# more_testing.net
KiCad netlist of a schematic drawn in EAGLE
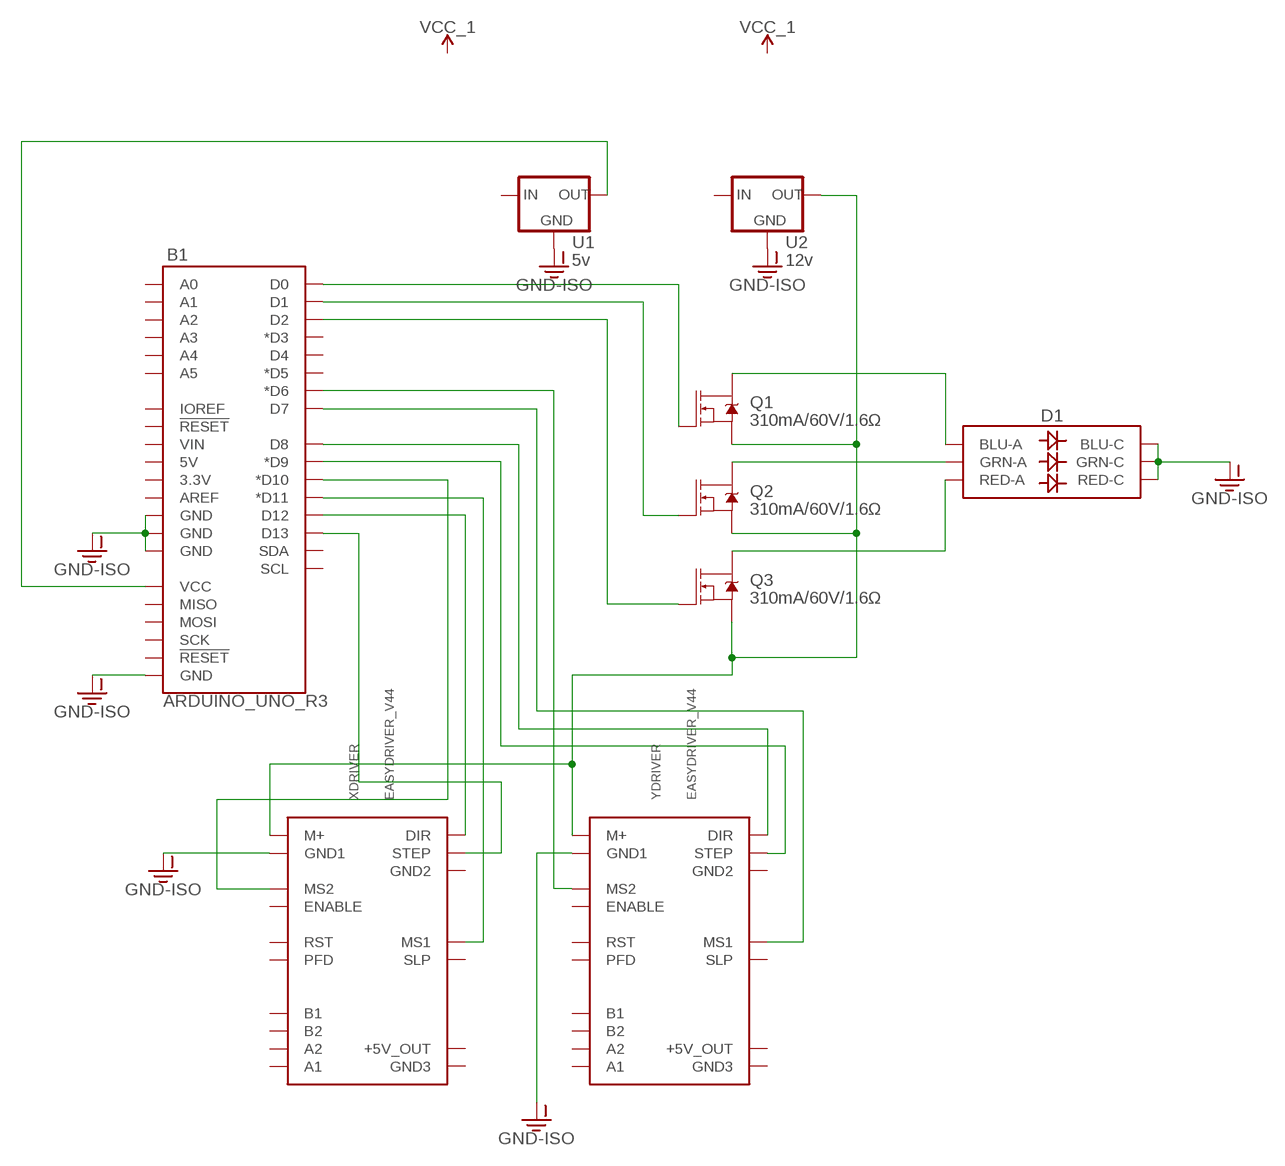
[diagram p0: schematic, sheet 1]

(export (version "E")
  (design (tool "Eeschema 10.0.6"))
  (components
    (comp (ref "B1")
      (value "ARDUINO_UNO_R3")
      (footprint "eagle-import:ARDUINO_R3")
      (libsource (lib "eagle-import") (part "ARDUINO_UNO_R3"))
    )
    (comp (ref "D1")
      (value "LED-RGBNO_IC")
      (footprint "eagle-import:LED-TRICOLOR-5050")
      (libsource (lib "eagle-import") (part "LED-RGBNO_IC"))
    )
    (comp (ref "Q1")
      (value "310mA/60V/1.6Ω")
      (footprint "eagle-import:SOT323")
      (libsource (lib "eagle-import") (part "MOSFET-NCH-2N7002PW"))
    )
    (comp (ref "Q2")
      (value "310mA/60V/1.6Ω")
      (footprint "eagle-import:SOT323")
      (libsource (lib "eagle-import") (part "MOSFET-NCH-2N7002PW"))
    )
    (comp (ref "Q3")
      (value "310mA/60V/1.6Ω")
      (footprint "eagle-import:SOT323")
      (libsource (lib "eagle-import") (part "MOSFET-NCH-2N7002PW"))
    )
    (comp (ref "U1")
      (value "5v")
      (footprint "eagle-import:78XXL")
      (libsource (lib "eagle-import") (part "V_REG_78XXSIDE"))
    )
    (comp (ref "U2")
      (value "12v")
      (footprint "eagle-import:78XXL")
      (libsource (lib "eagle-import") (part "V_REG_78XXSIDE"))
    )
    (comp (ref "XDRIVER")
      (value "EASYDRIVER_V44")
      (footprint "eagle-import:EASYDRIVER_V44")
      (libsource (lib "eagle-import") (part "EASYDRIVER_V44"))
    )
    (comp (ref "YDRIVER")
      (value "EASYDRIVER_V44")
      (footprint "eagle-import:EASYDRIVER_V44")
      (libsource (lib "eagle-import") (part "EASYDRIVER_V44"))
    )
  )
  (nets
    (net (code "1") (name "GND-ISO") (class "Default")
      (node (ref "B1") (pin "GND@1") (pinfunction "GND_GND@1") (pintype "bidirectional"))
      (node (ref "B1") (pin "GND@2") (pinfunction "GND_GND@2") (pintype "bidirectional"))
      (node (ref "B1") (pin "GND@3") (pinfunction "GND_GND@3") (pintype "bidirectional"))
      (node (ref "B1") (pin "GND@4") (pinfunction "GND_GND@4") (pintype "bidirectional"))
      (node (ref "D1") (pin "4") (pinfunction "BLU-C_4") (pintype "bidirectional"))
      (node (ref "D1") (pin "5") (pinfunction "RED-C_5") (pintype "bidirectional"))
      (node (ref "D1") (pin "6") (pinfunction "GRN-C_6") (pintype "bidirectional"))
      (node (ref "U1") (pin "GND") (pinfunction "GND_GND") (pintype "input"))
      (node (ref "U2") (pin "GND") (pinfunction "GND_GND") (pintype "input"))
      (node (ref "XDRIVER") (pin "GND1") (pinfunction "GND1_GND1") (pintype "bidirectional"))
      (node (ref "YDRIVER") (pin "GND1") (pinfunction "GND1_GND1") (pintype "bidirectional"))
    )
    (net (code "2") (name "Net-(B1-*D6)") (class "Default")
      (node (ref "B1") (pin "D6") (pinfunction "*D6_D6") (pintype "bidirectional"))
      (node (ref "YDRIVER") (pin "MS2") (pinfunction "MS2_MS2") (pintype "bidirectional"))
    )
    (net (code "3") (name "Net-(B1-*D9)") (class "Default")
      (node (ref "B1") (pin "D9") (pinfunction "*D9_D9") (pintype "bidirectional"))
      (node (ref "YDRIVER") (pin "STEP") (pinfunction "STEP_STEP") (pintype "bidirectional"))
    )
    (net (code "4") (name "Net-(B1-*D10)") (class "Default")
      (node (ref "B1") (pin "D10") (pinfunction "*D10_D10") (pintype "bidirectional"))
      (node (ref "XDRIVER") (pin "MS2") (pinfunction "MS2_MS2") (pintype "bidirectional"))
    )
    (net (code "5") (name "Net-(B1-*D11)") (class "Default")
      (node (ref "B1") (pin "D11") (pinfunction "*D11_D11") (pintype "bidirectional"))
      (node (ref "XDRIVER") (pin "MS1") (pinfunction "MS1_MS1") (pintype "bidirectional"))
    )
    (net (code "6") (name "Net-(B1-PadD7)") (class "Default")
      (node (ref "B1") (pin "D7") (pinfunction "D7_D7") (pintype "bidirectional"))
      (node (ref "YDRIVER") (pin "MS1") (pinfunction "MS1_MS1") (pintype "bidirectional"))
    )
    (net (code "7") (name "Net-(B1-PadD8)") (class "Default")
      (node (ref "B1") (pin "D8") (pinfunction "D8_D8") (pintype "bidirectional"))
      (node (ref "YDRIVER") (pin "DIR") (pinfunction "DIR_DIR") (pintype "bidirectional"))
    )
    (net (code "8") (name "Net-(B1-PadD12)") (class "Default")
      (node (ref "B1") (pin "D12") (pinfunction "D12_D12") (pintype "bidirectional"))
      (node (ref "XDRIVER") (pin "DIR") (pinfunction "DIR_DIR") (pintype "bidirectional"))
    )
    (net (code "9") (name "Net-(B1-PadD13)") (class "Default")
      (node (ref "B1") (pin "D13") (pinfunction "D13_D13") (pintype "bidirectional"))
      (node (ref "XDRIVER") (pin "STEP") (pinfunction "STEP_STEP") (pintype "bidirectional"))
    )
    (net (code "10") (name "Net-(B1-PadVCC)") (class "Default")
      (node (ref "B1") (pin "VCC") (pinfunction "VCC_VCC") (pintype "bidirectional"))
      (node (ref "U1") (pin "OUT") (pinfunction "OUT_OUT") (pintype "passive"))
    )
    (net (code "11") (name "Net-(D1-BLU-A)") (class "Default")
      (node (ref "D1") (pin "3") (pinfunction "BLU-A_3") (pintype "bidirectional"))
      (node (ref "Q1") (pin "3") (pinfunction "D_3") (pintype "bidirectional"))
    )
    (net (code "12") (name "Net-(D1-GRN-A)") (class "Default")
      (node (ref "D1") (pin "1") (pinfunction "GRN-A_1") (pintype "bidirectional"))
      (node (ref "Q2") (pin "3") (pinfunction "D_3") (pintype "bidirectional"))
    )
    (net (code "13") (name "Net-(D1-RED-A)") (class "Default")
      (node (ref "D1") (pin "2") (pinfunction "RED-A_2") (pintype "bidirectional"))
      (node (ref "Q3") (pin "3") (pinfunction "D_3") (pintype "bidirectional"))
    )
    (net (code "14") (name "Net-(Q1-G)") (class "Default")
      (node (ref "B1") (pin "D0") (pinfunction "D0_D0") (pintype "bidirectional"))
      (node (ref "Q1") (pin "1") (pinfunction "G_1") (pintype "bidirectional"))
    )
    (net (code "15") (name "Net-(Q1-S)") (class "Default")
      (node (ref "Q1") (pin "2") (pinfunction "S_2") (pintype "bidirectional"))
      (node (ref "Q2") (pin "2") (pinfunction "S_2") (pintype "bidirectional"))
      (node (ref "Q3") (pin "2") (pinfunction "S_2") (pintype "bidirectional"))
      (node (ref "U2") (pin "OUT") (pinfunction "OUT_OUT") (pintype "passive"))
      (node (ref "XDRIVER") (pin "M+") (pinfunction "M+_M+") (pintype "bidirectional"))
      (node (ref "YDRIVER") (pin "M+") (pinfunction "M+_M+") (pintype "bidirectional"))
    )
    (net (code "16") (name "Net-(Q2-G)") (class "Default")
      (node (ref "B1") (pin "D1") (pinfunction "D1_D1") (pintype "bidirectional"))
      (node (ref "Q2") (pin "1") (pinfunction "G_1") (pintype "bidirectional"))
    )
    (net (code "17") (name "Net-(Q3-G)") (class "Default")
      (node (ref "B1") (pin "D2") (pinfunction "D2_D2") (pintype "bidirectional"))
      (node (ref "Q3") (pin "1") (pinfunction "G_1") (pintype "bidirectional"))
    )
    (net (code "19") (name "unconnected-(B1-*D3-PadD3)") (class "Default")
      (node (ref "B1") (pin "D3") (pinfunction "*D3_D3") (pintype "bidirectional"))
    )
    (net (code "20") (name "unconnected-(B1-*D5-PadD5)") (class "Default")
      (node (ref "B1") (pin "D5") (pinfunction "*D5_D5") (pintype "bidirectional"))
    )
    (net (code "21") (name "unconnected-(B1-Pad3.3V)") (class "Default")
      (node (ref "B1") (pin "3.3V") (pinfunction "3.3V_3.3V") (pintype "bidirectional"))
    )
    (net (code "22") (name "unconnected-(B1-Pad5V)") (class "Default")
      (node (ref "B1") (pin "5V") (pinfunction "5V_5V") (pintype "bidirectional"))
    )
    (net (code "23") (name "unconnected-(B1-PadA0)") (class "Default")
      (node (ref "B1") (pin "A0") (pinfunction "A0_A0") (pintype "bidirectional"))
    )
    (net (code "24") (name "unconnected-(B1-PadA1)") (class "Default")
      (node (ref "B1") (pin "A1") (pinfunction "A1_A1") (pintype "bidirectional"))
    )
    (net (code "25") (name "unconnected-(B1-PadA2)") (class "Default")
      (node (ref "B1") (pin "A2") (pinfunction "A2_A2") (pintype "bidirectional"))
    )
    (net (code "26") (name "unconnected-(B1-PadA3)") (class "Default")
      (node (ref "B1") (pin "A3") (pinfunction "A3_A3") (pintype "bidirectional"))
    )
    (net (code "27") (name "unconnected-(B1-PadA4)") (class "Default")
      (node (ref "B1") (pin "A4") (pinfunction "A4_A4") (pintype "bidirectional"))
    )
    (net (code "28") (name "unconnected-(B1-PadA5)") (class "Default")
      (node (ref "B1") (pin "A5") (pinfunction "A5_A5") (pintype "bidirectional"))
    )
    (net (code "29") (name "unconnected-(B1-PadAREF)") (class "Default")
      (node (ref "B1") (pin "AREF") (pinfunction "AREF_AREF") (pintype "bidirectional"))
    )
    (net (code "30") (name "unconnected-(B1-PadD4)") (class "Default")
      (node (ref "B1") (pin "D4") (pinfunction "D4_D4") (pintype "bidirectional"))
    )
    (net (code "31") (name "unconnected-(B1-PadIOREF)") (class "Default")
      (node (ref "B1") (pin "IOREF") (pinfunction "IOREF_IOREF") (pintype "bidirectional"))
    )
    (net (code "32") (name "unconnected-(B1-PadMISO)") (class "Default")
      (node (ref "B1") (pin "MISO") (pinfunction "MISO_MISO") (pintype "bidirectional"))
    )
    (net (code "33") (name "unconnected-(B1-PadMOSI)") (class "Default")
      (node (ref "B1") (pin "MOSI") (pinfunction "MOSI_MOSI") (pintype "bidirectional"))
    )
    (net (code "34") (name "unconnected-(B1-PadSCK)") (class "Default")
      (node (ref "B1") (pin "SCK") (pinfunction "SCK_SCK") (pintype "bidirectional"))
    )
    (net (code "35") (name "unconnected-(B1-PadSCL)") (class "Default")
      (node (ref "B1") (pin "SCL") (pinfunction "SCL_SCL") (pintype "bidirectional"))
    )
    (net (code "36") (name "unconnected-(B1-PadSDA)") (class "Default")
      (node (ref "B1") (pin "SDA") (pinfunction "SDA_SDA") (pintype "bidirectional"))
    )
    (net (code "37") (name "unconnected-(B1-PadVIN)") (class "Default")
      (node (ref "B1") (pin "VIN") (pinfunction "VIN_VIN") (pintype "bidirectional"))
    )
    (net (code "38") (name "unconnected-(B1-~{RESET}-PadRESET@1)") (class "Default")
      (node (ref "B1") (pin "RESET@1") (pinfunction "~{RESET}_RESET@1") (pintype "bidirectional"))
    )
    (net (code "39") (name "unconnected-(B1-~{RESET}-PadRESET@2)") (class "Default")
      (node (ref "B1") (pin "RESET@2") (pinfunction "~{RESET}_RESET@2") (pintype "bidirectional"))
    )
    (net (code "40") (name "unconnected-(U1-PadIN)") (class "Default")
      (node (ref "U1") (pin "IN") (pinfunction "IN_IN") (pintype "input"))
    )
    (net (code "41") (name "unconnected-(U2-PadIN)") (class "Default")
      (node (ref "U2") (pin "IN") (pinfunction "IN_IN") (pintype "input"))
    )
    (net (code "42") (name "unconnected-(XDRIVER-+5V_OUT-PadP$11)") (class "Default")
      (node (ref "XDRIVER") (pin "P$11") (pinfunction "+5V_OUT_P$11") (pintype "bidirectional"))
    )
    (net (code "43") (name "unconnected-(XDRIVER-PadA1)") (class "Default")
      (node (ref "XDRIVER") (pin "A1") (pinfunction "A1_A1") (pintype "bidirectional"))
    )
    (net (code "44") (name "unconnected-(XDRIVER-PadA2)") (class "Default")
      (node (ref "XDRIVER") (pin "A2") (pinfunction "A2_A2") (pintype "bidirectional"))
    )
    (net (code "45") (name "unconnected-(XDRIVER-PadB1)") (class "Default")
      (node (ref "XDRIVER") (pin "B1") (pinfunction "B1_B1") (pintype "bidirectional"))
    )
    (net (code "46") (name "unconnected-(XDRIVER-PadB2)") (class "Default")
      (node (ref "XDRIVER") (pin "B2") (pinfunction "B2_B2") (pintype "bidirectional"))
    )
    (net (code "47") (name "unconnected-(XDRIVER-PadENABLE)") (class "Default")
      (node (ref "XDRIVER") (pin "ENABLE") (pinfunction "ENABLE_ENABLE") (pintype "bidirectional"))
    )
    (net (code "48") (name "unconnected-(XDRIVER-PadGND2)") (class "Default")
      (node (ref "XDRIVER") (pin "GND2") (pinfunction "GND2_GND2") (pintype "bidirectional"))
    )
    (net (code "49") (name "unconnected-(XDRIVER-PadGND3)") (class "Default")
      (node (ref "XDRIVER") (pin "GND3") (pinfunction "GND3_GND3") (pintype "bidirectional"))
    )
    (net (code "50") (name "unconnected-(XDRIVER-PadPFD)") (class "Default")
      (node (ref "XDRIVER") (pin "PFD") (pinfunction "PFD_PFD") (pintype "bidirectional"))
    )
    (net (code "51") (name "unconnected-(XDRIVER-PadRST)") (class "Default")
      (node (ref "XDRIVER") (pin "RST") (pinfunction "RST_RST") (pintype "bidirectional"))
    )
    (net (code "52") (name "unconnected-(XDRIVER-SLP-PadSLEEP)") (class "Default")
      (node (ref "XDRIVER") (pin "SLEEP") (pinfunction "SLP_SLEEP") (pintype "bidirectional"))
    )
    (net (code "53") (name "unconnected-(YDRIVER-+5V_OUT-PadP$11)") (class "Default")
      (node (ref "YDRIVER") (pin "P$11") (pinfunction "+5V_OUT_P$11") (pintype "bidirectional"))
    )
    (net (code "54") (name "unconnected-(YDRIVER-PadA1)") (class "Default")
      (node (ref "YDRIVER") (pin "A1") (pinfunction "A1_A1") (pintype "bidirectional"))
    )
    (net (code "55") (name "unconnected-(YDRIVER-PadA2)") (class "Default")
      (node (ref "YDRIVER") (pin "A2") (pinfunction "A2_A2") (pintype "bidirectional"))
    )
    (net (code "56") (name "unconnected-(YDRIVER-PadB1)") (class "Default")
      (node (ref "YDRIVER") (pin "B1") (pinfunction "B1_B1") (pintype "bidirectional"))
    )
    (net (code "57") (name "unconnected-(YDRIVER-PadB2)") (class "Default")
      (node (ref "YDRIVER") (pin "B2") (pinfunction "B2_B2") (pintype "bidirectional"))
    )
    (net (code "58") (name "unconnected-(YDRIVER-PadENABLE)") (class "Default")
      (node (ref "YDRIVER") (pin "ENABLE") (pinfunction "ENABLE_ENABLE") (pintype "bidirectional"))
    )
    (net (code "59") (name "unconnected-(YDRIVER-PadGND2)") (class "Default")
      (node (ref "YDRIVER") (pin "GND2") (pinfunction "GND2_GND2") (pintype "bidirectional"))
    )
    (net (code "60") (name "unconnected-(YDRIVER-PadGND3)") (class "Default")
      (node (ref "YDRIVER") (pin "GND3") (pinfunction "GND3_GND3") (pintype "bidirectional"))
    )
    (net (code "61") (name "unconnected-(YDRIVER-PadPFD)") (class "Default")
      (node (ref "YDRIVER") (pin "PFD") (pinfunction "PFD_PFD") (pintype "bidirectional"))
    )
    (net (code "62") (name "unconnected-(YDRIVER-PadRST)") (class "Default")
      (node (ref "YDRIVER") (pin "RST") (pinfunction "RST_RST") (pintype "bidirectional"))
    )
    (net (code "63") (name "unconnected-(YDRIVER-SLP-PadSLEEP)") (class "Default")
      (node (ref "YDRIVER") (pin "SLEEP") (pinfunction "SLP_SLEEP") (pintype "bidirectional"))
    )
  )
)
